# SCH_Electric_Target_2022-06-11.net
KiCad netlist of a schematic drawn in EasyEDA
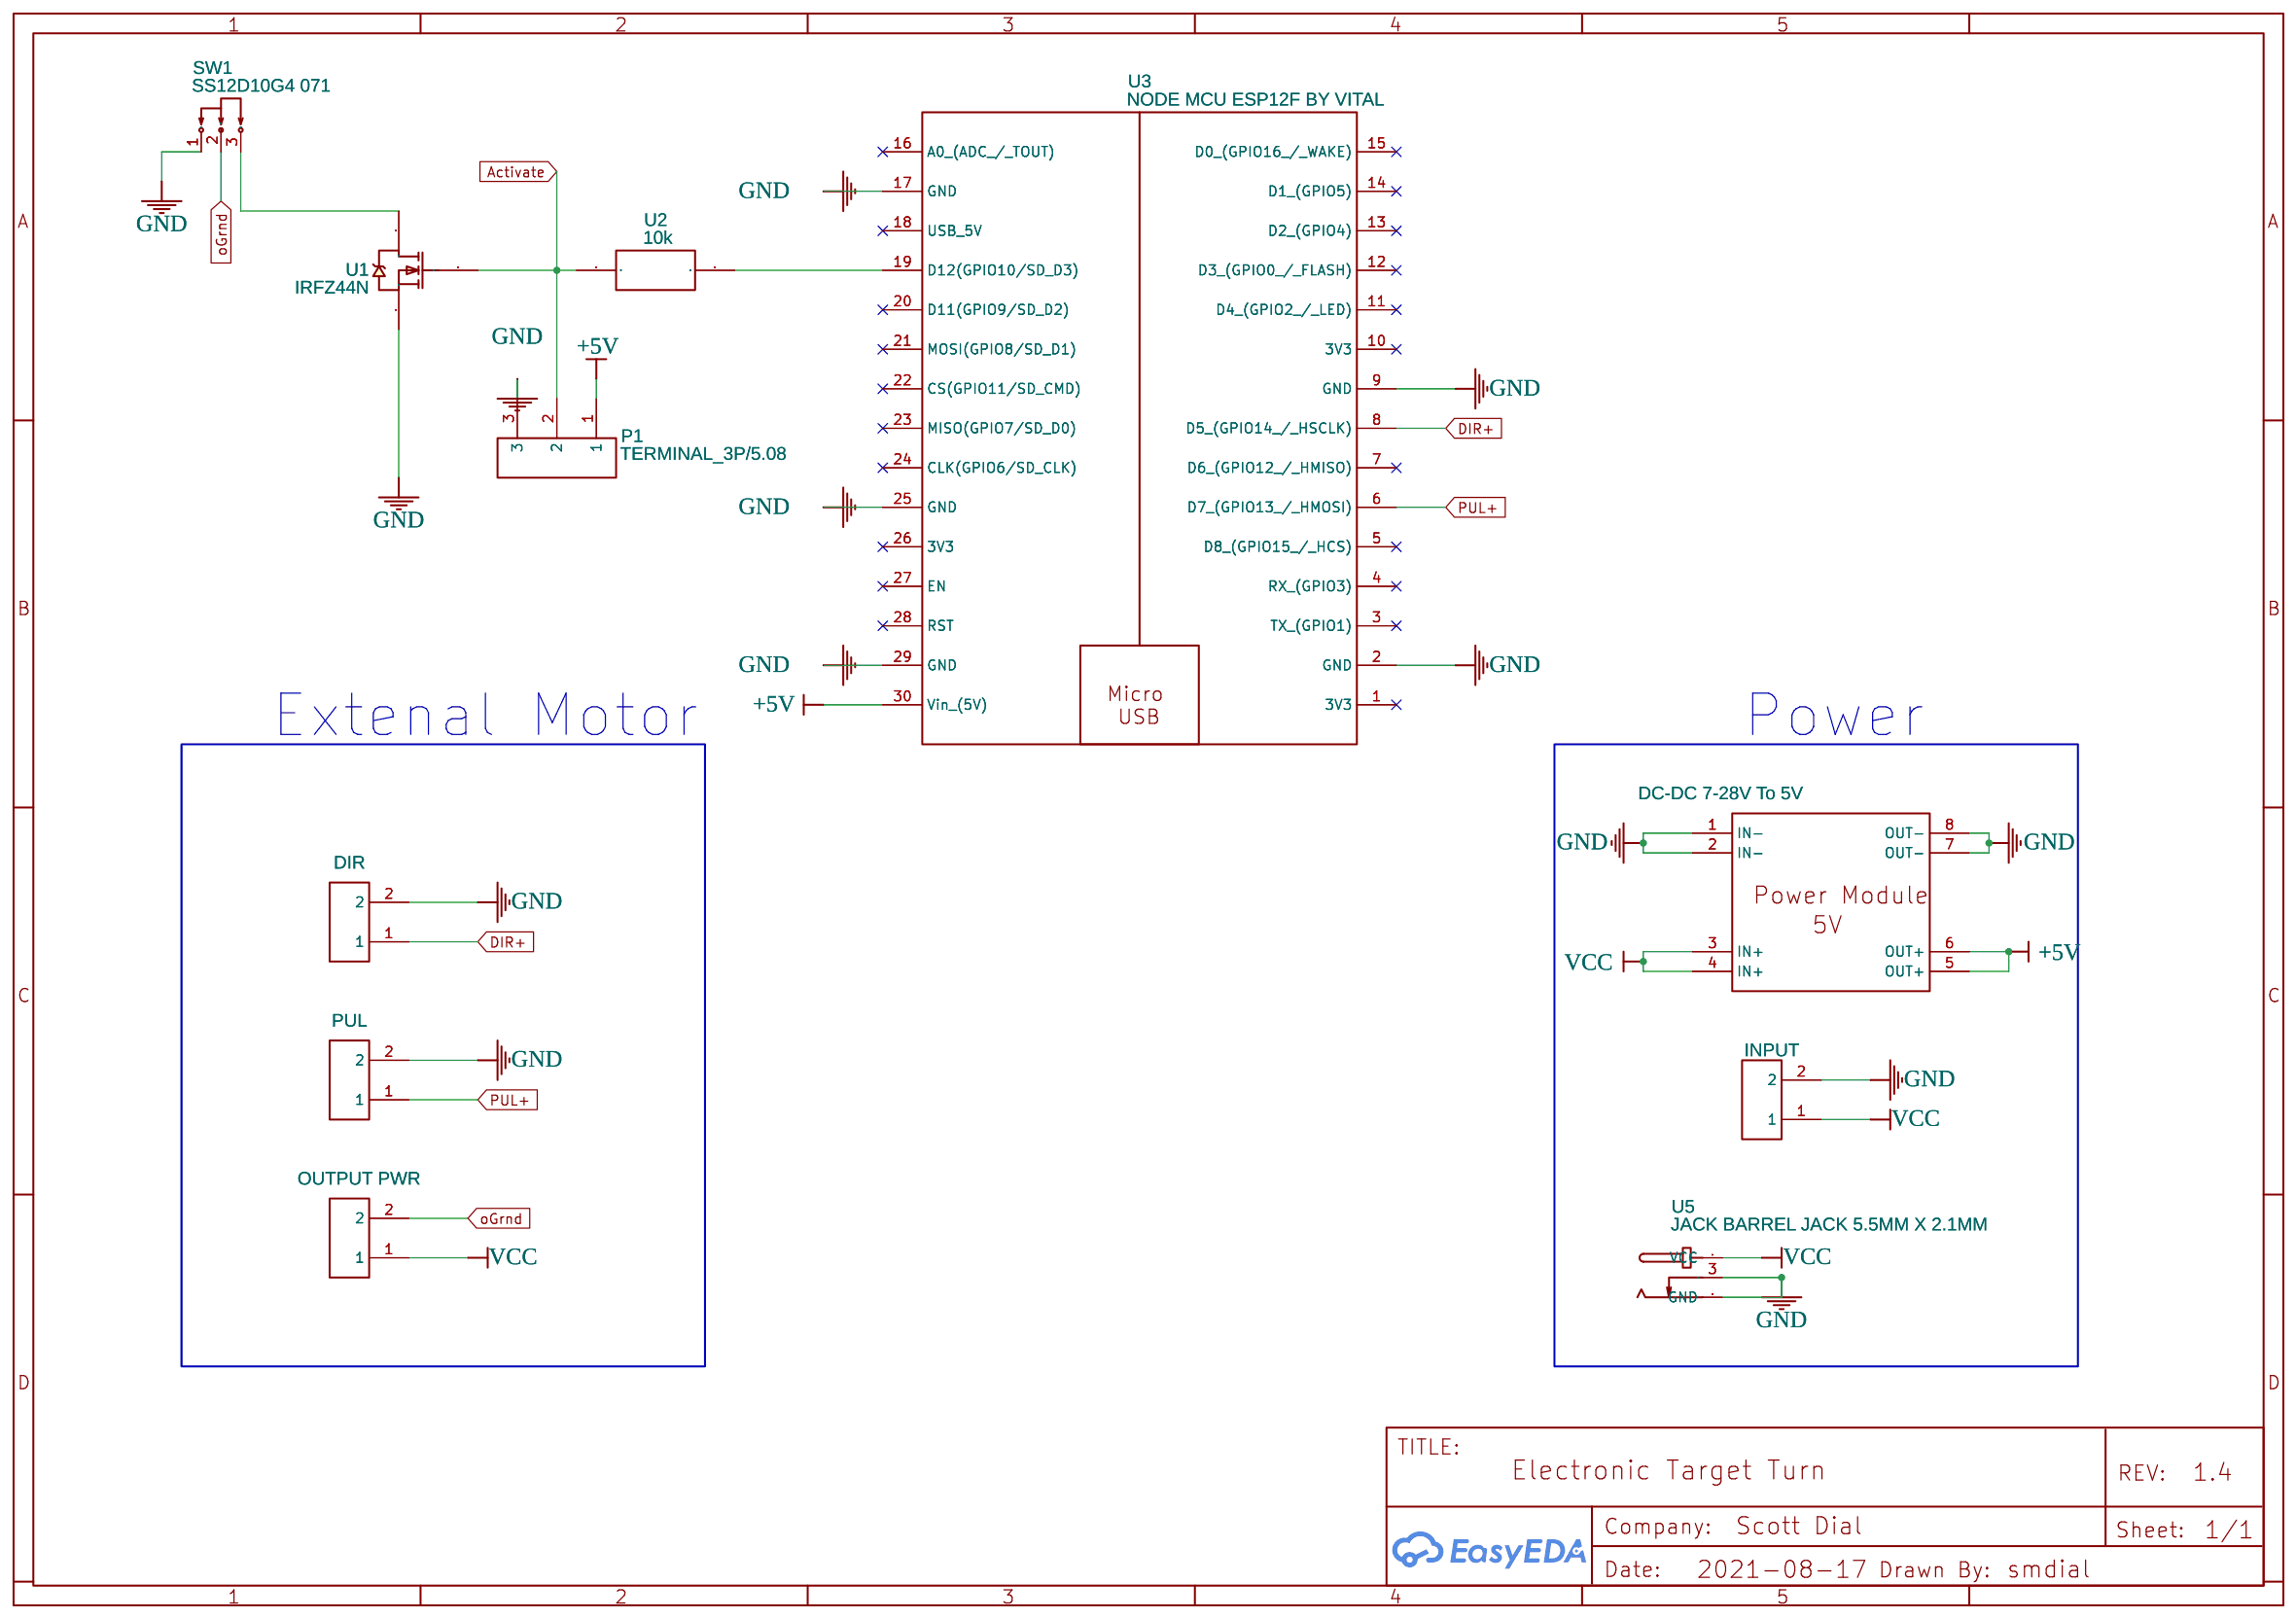
[diagram p0: schematic sheet]

(export (version "E")
  (design (tool "Eeschema 10.0.6"))
  (components
    (comp (ref "P1")
      (value "TERMINAL_3P/5.08")
      (fields (field (name "BOM_Manufacturer Part") "Screw terminal 3p"))
      (libsource (lib "") (part "TERMINAL_3P/5.08"))
    )
    (comp (ref "P2")
      (value "DIR")
      (fields (field (name "BOM_Manufacturer Part") "Screw terminal 2p"))
      (libsource (lib "") (part "SCREW TERMINAL 2P"))
    )
    (comp (ref "P5")
      (value "PUL")
      (fields (field (name "BOM_Manufacturer Part") "Screw terminal 2p"))
      (libsource (lib "") (part "SCREW TERMINAL 2P"))
    )
    (comp (ref "P6")
      (value "INPUT")
      (fields (field (name "BOM_Manufacturer Part") "Screw terminal 2p"))
      (libsource (lib "") (part "SCREW TERMINAL 2P"))
    )
    (comp (ref "P7")
      (value "OUTPUT PWR")
      (fields (field (name "BOM_Manufacturer Part") "Screw terminal 2p"))
      (libsource (lib "") (part "SCREW TERMINAL 2P"))
    )
    (comp (ref "SW1")
      (value "SS12D10G4 071")
      (fields (field (name "BOM_Supplier Part") "C2887259"))
      (libsource (lib "") (part "SS12D10G4 071"))
    )
    (comp (ref "U1") (value "IRFZ44N") (libsource (lib "") (part "IRFZ44N")))
    (comp (ref "U2") (value "10k") (libsource (lib "") (part "RESISTOR")))
    (comp (ref "U3")
      (value "NODE MCU ESP12F BY VITAL")
      (libsource (lib "") (part "NODE MCU ESP12F BY VITAL"))
    )
    (comp (ref "U4")
      (value "DC-DC 7-28V To 5V")
      (fields (field (name "BOM_Manufacturer Part") "DC-DC 7-28V To 5V Step Down Power Supply Module"))
      (libsource (lib "") (part "DC-DC 7-28V To 5V Step Down Power Supply Module"))
    )
    (comp (ref "U5")
      (value "JACK BARREL JACK 5.5MM X 2.1MM")
      (libsource (lib "") (part "JACK BARREL JACK 5.5MM X 2.1MM"))
    )
  )
  (nets
    (net (code "1") (name "+5V") (class "Default")
      (node (ref "P1") (pin "1") (pinfunction "1_1") (pintype "unspecified"))
      (node (ref "U3") (pin "30") (pinfunction "Vin_(5V)_30") (pintype "unspecified"))
      (node (ref "U4") (pin "5") (pinfunction "OUT+_5") (pintype "unspecified"))
      (node (ref "U4") (pin "6") (pinfunction "OUT+_6") (pintype "unspecified"))
    )
    (net (code "2") (name "Activate") (class "Default")
      (node (ref "P1") (pin "2") (pinfunction "2_2") (pintype "unspecified"))
      (node (ref "U1") (pin "1") (pinfunction "G_1") (pintype "unspecified"))
      (node (ref "U2") (pin "2") (pinfunction "2_2") (pintype "unspecified"))
    )
    (net (code "3") (name "DIR+") (class "Default")
      (node (ref "P2") (pin "1") (pinfunction "1_1") (pintype "unspecified"))
      (node (ref "U3") (pin "8") (pinfunction "D5_(GPIO14_/_HSCLK)_8") (pintype "unspecified"))
    )
    (net (code "4") (name "GND") (class "Default")
      (node (ref "P1") (pin "3") (pinfunction "3_3") (pintype "unspecified"))
      (node (ref "P2") (pin "2") (pinfunction "2_2") (pintype "unspecified"))
      (node (ref "P5") (pin "2") (pinfunction "2_2") (pintype "unspecified"))
      (node (ref "P6") (pin "2") (pinfunction "2_2") (pintype "unspecified"))
      (node (ref "SW1") (pin "1") (pinfunction "1_1") (pintype "unspecified"))
      (node (ref "U1") (pin "3") (pinfunction "S_3") (pintype "unspecified"))
      (node (ref "U3") (pin "17") (pinfunction "GND_17") (pintype "unspecified"))
      (node (ref "U3") (pin "2") (pinfunction "GND_2") (pintype "unspecified"))
      (node (ref "U3") (pin "25") (pinfunction "GND_25") (pintype "unspecified"))
      (node (ref "U3") (pin "29") (pinfunction "GND_29") (pintype "unspecified"))
      (node (ref "U3") (pin "9") (pinfunction "GND_9") (pintype "unspecified"))
      (node (ref "U4") (pin "1") (pinfunction "IN-_1") (pintype "unspecified"))
      (node (ref "U4") (pin "2") (pinfunction "IN-_2") (pintype "unspecified"))
      (node (ref "U4") (pin "7") (pinfunction "OUT-_7") (pintype "unspecified"))
      (node (ref "U4") (pin "8") (pinfunction "OUT-_8") (pintype "unspecified"))
      (node (ref "U5") (pin "2") (pinfunction "GND_2") (pintype "passive"))
      (node (ref "U5") (pin "3") (pinfunction "3_3") (pintype "passive"))
    )
    (net (code "5") (name "Net-(U1-D)") (class "Default")
      (node (ref "SW1") (pin "3") (pinfunction "3_3") (pintype "unspecified"))
      (node (ref "U1") (pin "2") (pinfunction "D_2") (pintype "unspecified"))
    )
    (net (code "6") (name "Net-(U3-D12(GPIO10{slash}SD_D3))") (class "Default")
      (node (ref "U2") (pin "1") (pinfunction "1_1") (pintype "unspecified"))
      (node (ref "U3") (pin "19") (pinfunction "D12(GPIO10/SD_D3)_19") (pintype "unspecified"))
    )
    (net (code "7") (name "PUL+") (class "Default")
      (node (ref "P5") (pin "1") (pinfunction "1_1") (pintype "unspecified"))
      (node (ref "U3") (pin "6") (pinfunction "D7_(GPIO13_/_HMOSI)_6") (pintype "unspecified"))
    )
    (net (code "8") (name "VCC") (class "Default")
      (node (ref "P6") (pin "1") (pinfunction "1_1") (pintype "unspecified"))
      (node (ref "P7") (pin "1") (pinfunction "1_1") (pintype "unspecified"))
      (node (ref "U4") (pin "3") (pinfunction "IN+_3") (pintype "unspecified"))
      (node (ref "U4") (pin "4") (pinfunction "IN+_4") (pintype "unspecified"))
      (node (ref "U5") (pin "1") (pinfunction "VCC_1") (pintype "passive"))
    )
    (net (code "9") (name "oGrnd") (class "Default")
      (node (ref "P7") (pin "2") (pinfunction "2_2") (pintype "unspecified"))
      (node (ref "SW1") (pin "2") (pinfunction "2_2") (pintype "unspecified"))
    )
    (net (code "10") (name "unconnected-(U3-3V3-Pad1)") (class "Default")
      (node (ref "U3") (pin "1") (pinfunction "3V3_1") (pintype "unspecified+no_connect"))
    )
    (net (code "11") (name "unconnected-(U3-3V3-Pad10)") (class "Default")
      (node (ref "U3") (pin "10") (pinfunction "3V3_10") (pintype "unspecified+no_connect"))
    )
    (net (code "12") (name "unconnected-(U3-3V3-Pad26)") (class "Default")
      (node (ref "U3") (pin "26") (pinfunction "3V3_26") (pintype "unspecified+no_connect"))
    )
    (net (code "13") (name "unconnected-(U3-A0_(ADC_{slash}_TOUT)-Pad16)") (class "Default")
      (node (ref "U3") (pin "16") (pinfunction "A0_(ADC_/_TOUT)_16") (pintype "unspecified+no_connect"))
    )
    (net (code "14") (name "unconnected-(U3-CLK(GPIO6{slash}SD_CLK)-Pad24)") (class "Default")
      (node (ref "U3") (pin "24") (pinfunction "CLK(GPIO6/SD_CLK)_24") (pintype "unspecified+no_connect"))
    )
    (net (code "15") (name "unconnected-(U3-CS(GPIO11{slash}SD_CMD)-Pad22)") (class "Default")
      (node (ref "U3") (pin "22") (pinfunction "CS(GPIO11/SD_CMD)_22") (pintype "unspecified+no_connect"))
    )
    (net (code "16") (name "unconnected-(U3-D0_(GPIO16_{slash}_WAKE)-Pad15)") (class "Default")
      (node (ref "U3") (pin "15") (pinfunction "D0_(GPIO16_/_WAKE)_15") (pintype "unspecified+no_connect"))
    )
    (net (code "17") (name "unconnected-(U3-D1_(GPIO5)-Pad14)") (class "Default")
      (node (ref "U3") (pin "14") (pinfunction "D1_(GPIO5)_14") (pintype "unspecified+no_connect"))
    )
    (net (code "18") (name "unconnected-(U3-D2_(GPIO4)-Pad13)") (class "Default")
      (node (ref "U3") (pin "13") (pinfunction "D2_(GPIO4)_13") (pintype "unspecified+no_connect"))
    )
    (net (code "19") (name "unconnected-(U3-D3_(GPIO0_{slash}_FLASH)-Pad12)") (class "Default")
      (node (ref "U3") (pin "12") (pinfunction "D3_(GPIO0_/_FLASH)_12") (pintype "unspecified+no_connect"))
    )
    (net (code "20") (name "unconnected-(U3-D4_(GPIO2_{slash}_LED)-Pad11)") (class "Default")
      (node (ref "U3") (pin "11") (pinfunction "D4_(GPIO2_/_LED)_11") (pintype "unspecified+no_connect"))
    )
    (net (code "21") (name "unconnected-(U3-D6_(GPIO12_{slash}_HMISO)-Pad7)") (class "Default")
      (node (ref "U3") (pin "7") (pinfunction "D6_(GPIO12_/_HMISO)_7") (pintype "unspecified+no_connect"))
    )
    (net (code "22") (name "unconnected-(U3-D8_(GPIO15_{slash}_HCS)-Pad5)") (class "Default")
      (node (ref "U3") (pin "5") (pinfunction "D8_(GPIO15_/_HCS)_5") (pintype "unspecified+no_connect"))
    )
    (net (code "23") (name "unconnected-(U3-D11(GPIO9{slash}SD_D2)-Pad20)") (class "Default")
      (node (ref "U3") (pin "20") (pinfunction "D11(GPIO9/SD_D2)_20") (pintype "unspecified+no_connect"))
    )
    (net (code "24") (name "unconnected-(U3-EN-Pad27)") (class "Default")
      (node (ref "U3") (pin "27") (pinfunction "EN_27") (pintype "unspecified+no_connect"))
    )
    (net (code "25") (name "unconnected-(U3-MISO(GPIO7{slash}SD_D0)-Pad23)") (class "Default")
      (node (ref "U3") (pin "23") (pinfunction "MISO(GPIO7/SD_D0)_23") (pintype "unspecified+no_connect"))
    )
    (net (code "26") (name "unconnected-(U3-MOSI(GPIO8{slash}SD_D1)-Pad21)") (class "Default")
      (node (ref "U3") (pin "21") (pinfunction "MOSI(GPIO8/SD_D1)_21") (pintype "unspecified+no_connect"))
    )
    (net (code "27") (name "unconnected-(U3-RST-Pad28)") (class "Default")
      (node (ref "U3") (pin "28") (pinfunction "RST_28") (pintype "unspecified+no_connect"))
    )
    (net (code "28") (name "unconnected-(U3-RX_(GPIO3)-Pad4)") (class "Default")
      (node (ref "U3") (pin "4") (pinfunction "RX_(GPIO3)_4") (pintype "unspecified+no_connect"))
    )
    (net (code "29") (name "unconnected-(U3-TX_(GPIO1)-Pad3)") (class "Default")
      (node (ref "U3") (pin "3") (pinfunction "TX_(GPIO1)_3") (pintype "unspecified+no_connect"))
    )
    (net (code "30") (name "unconnected-(U3-USB_5V-Pad18)") (class "Default")
      (node (ref "U3") (pin "18") (pinfunction "USB_5V_18") (pintype "unspecified+no_connect"))
    )
  )
)
